# Sheet1.net
KiCad netlist of a schematic drawn in Altium Designer
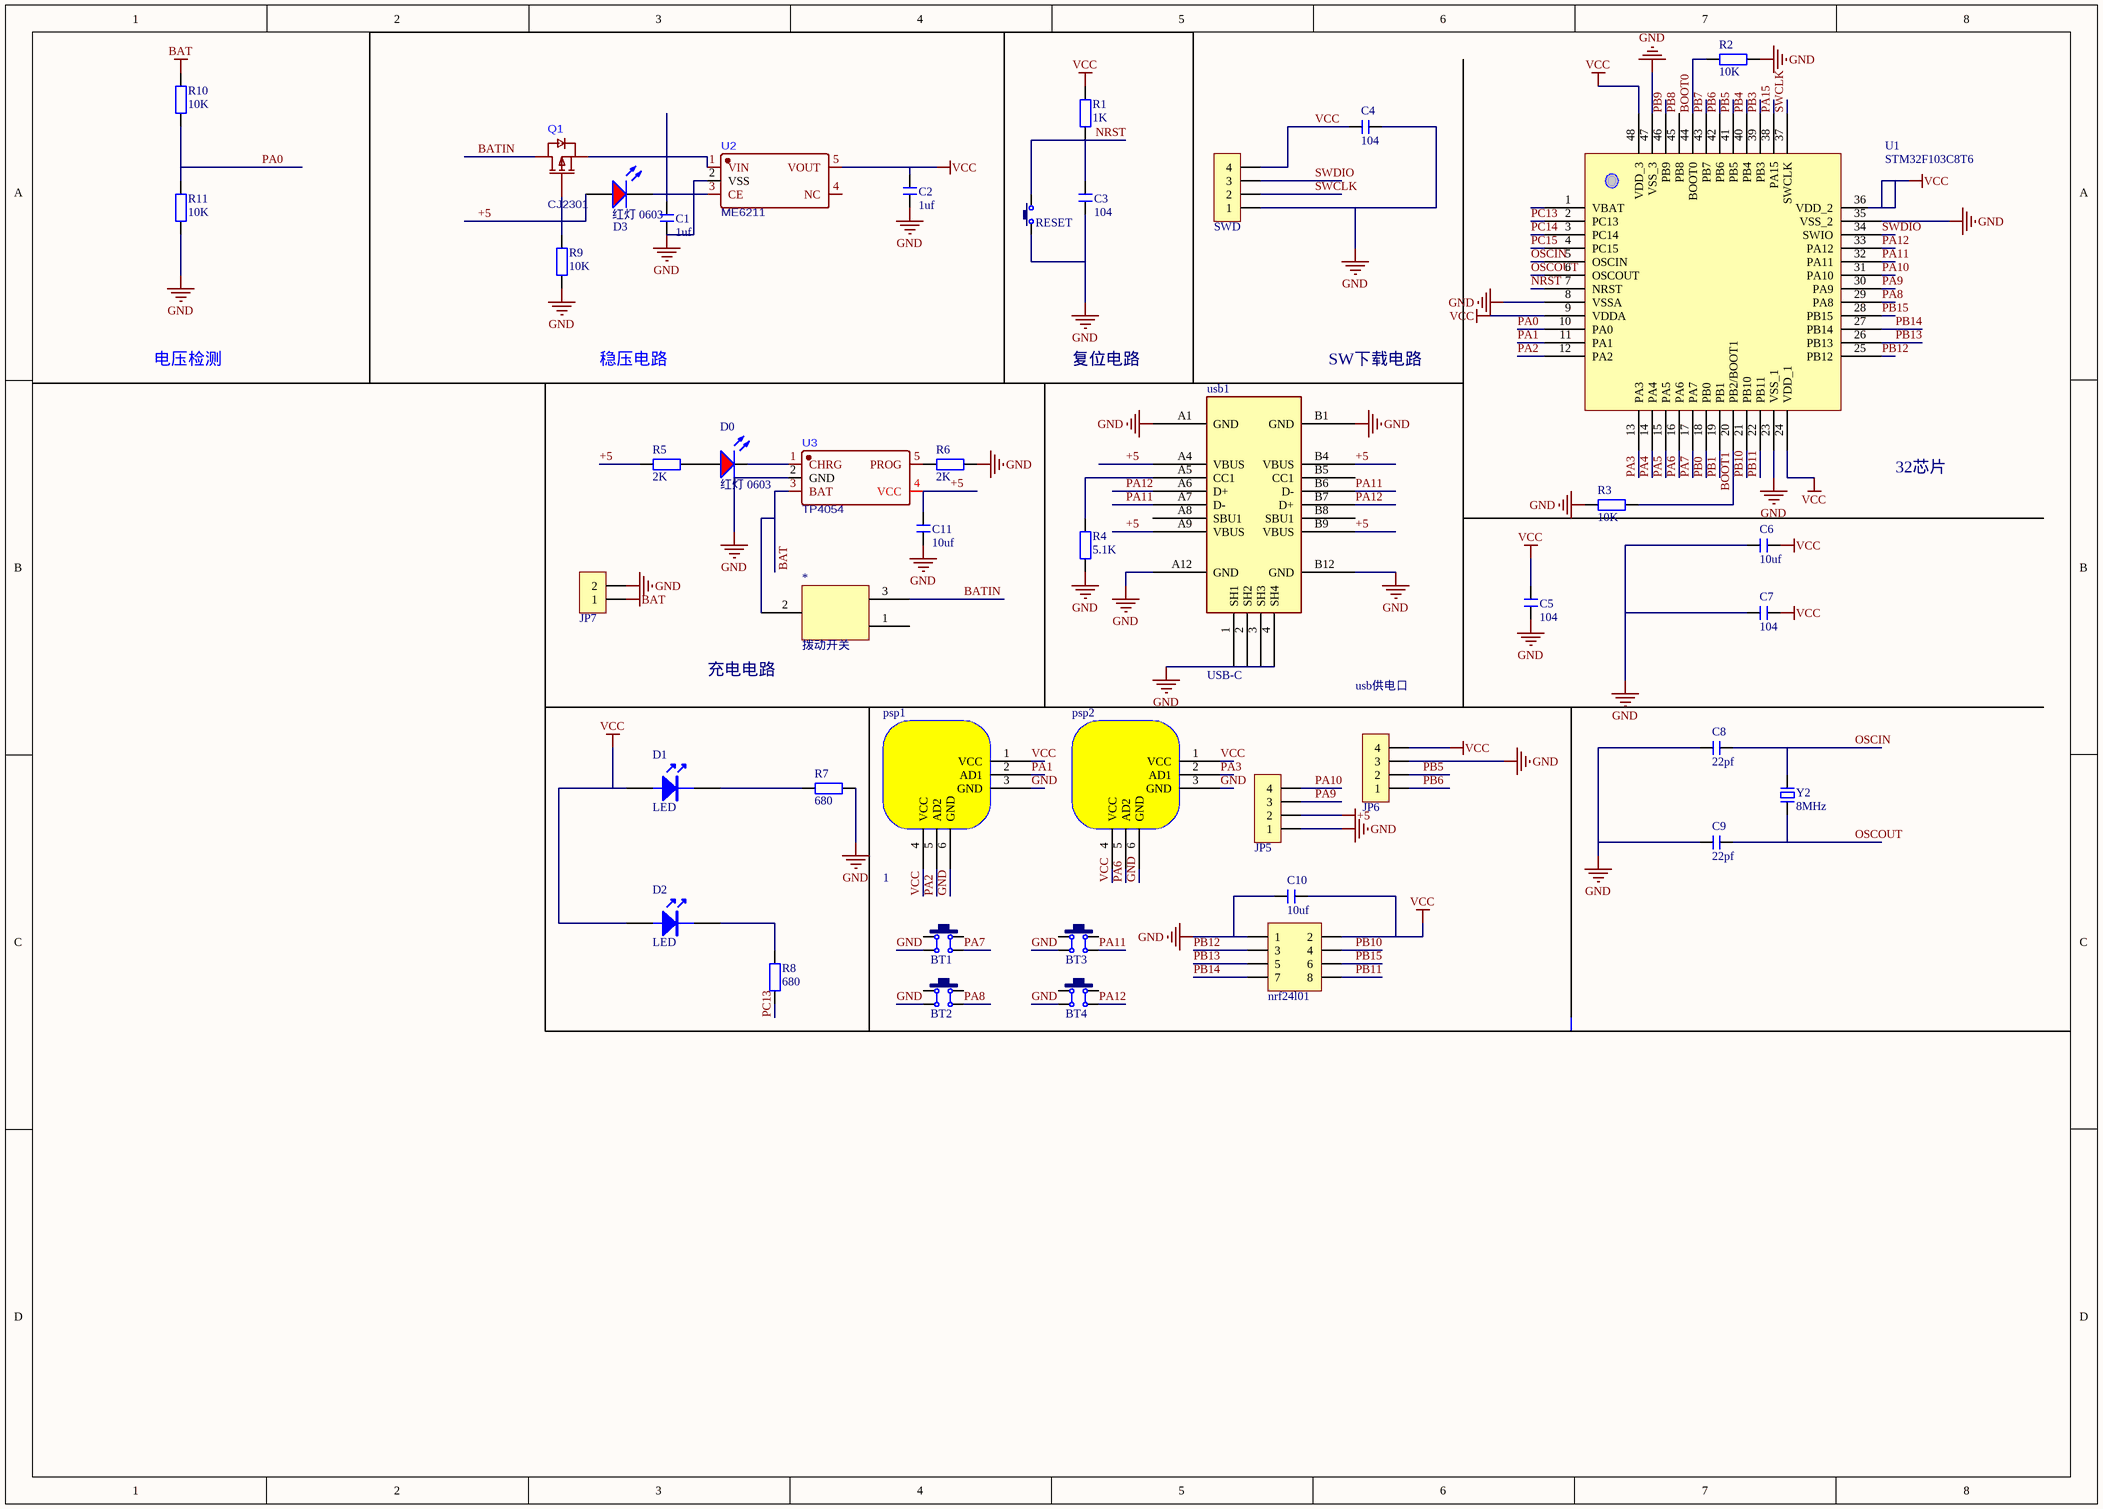
[diagram p0: Sheet1.SchDoc]

(export (version "E")
  (design (tool "Eeschema 10.0.6"))
  (components
    (comp (ref "*") (value "拨动开关") (footprint "SS-12F23") (libsource (lib "拨动开关") (part "拨动开关")))
    (comp (ref "BT1")
      (value "6x6x5")
      (footprint "TSW DIP-6*6*6")
      (description "直插6x6轻触开关")
      (fields (field (name "版权归属") "封装库来自淘宝 ID：黄晶宝石"))
      (libsource (lib "0.7 - 常用按键-开关") (part "TSW DIP-6x6"))
    )
    (comp (ref "BT2")
      (value "6x6x5")
      (footprint "TSW DIP-6*6*6")
      (description "直插6x6轻触开关")
      (fields (field (name "版权归属") "封装库来自淘宝 ID：黄晶宝石"))
      (libsource (lib "0.7 - 常用按键-开关") (part "TSW DIP-6x6"))
    )
    (comp (ref "BT3")
      (value "6x6x5")
      (footprint "TSW DIP-6*6*6")
      (description "直插6x6轻触开关")
      (fields (field (name "版权归属") "封装库来自淘宝 ID：黄晶宝石"))
      (libsource (lib "0.7 - 常用按键-开关") (part "TSW DIP-6x6"))
    )
    (comp (ref "BT4")
      (value "6x6x5")
      (footprint "TSW DIP-6*6*6")
      (description "直插6x6轻触开关")
      (fields (field (name "版权归属") "封装库来自淘宝 ID：黄晶宝石"))
      (libsource (lib "0.7 - 常用按键-开关") (part "TSW DIP-6x6"))
    )
    (comp (ref "C1")
      (value "1uf")
      (footprint "C 0603_L")
      (description "贴片电容")
      (libsource (lib "0.1 - 电阻-电容-电感") (part "C"))
    )
    (comp (ref "C2")
      (value "1uf")
      (footprint "C 0603_L")
      (description "贴片电容")
      (libsource (lib "0.1 - 电阻-电容-电感") (part "C"))
    )
    (comp (ref "C3")
      (value "104")
      (footprint "C 0603_L")
      (description "贴片电容")
      (libsource (lib "0.1 - 电阻-电容-电感") (part "C"))
    )
    (comp (ref "C4")
      (value "104")
      (footprint "C 0603_L")
      (description "贴片电容")
      (libsource (lib "0.1 - 电阻-电容-电感") (part "C"))
    )
    (comp (ref "C5")
      (value "104")
      (footprint "C 0603_L")
      (description "贴片电容")
      (libsource (lib "0.1 - 电阻-电容-电感") (part "C"))
    )
    (comp (ref "C6")
      (value "10uf")
      (footprint "C 0603_L")
      (description "贴片电容")
      (libsource (lib "0.1 - 电阻-电容-电感") (part "C"))
    )
    (comp (ref "C7")
      (value "104")
      (footprint "C 0603_L")
      (description "贴片电容")
      (libsource (lib "0.1 - 电阻-电容-电感") (part "C"))
    )
    (comp (ref "C8")
      (value "22pf")
      (footprint "C 0603_L")
      (description "贴片电容")
      (libsource (lib "0.1 - 电阻-电容-电感") (part "C"))
    )
    (comp (ref "C9")
      (value "22pf")
      (footprint "C 0603_L")
      (description "贴片电容")
      (libsource (lib "0.1 - 电阻-电容-电感") (part "C"))
    )
    (comp (ref "C10")
      (value "10uf")
      (footprint "C 0603_L")
      (description "贴片电容")
      (libsource (lib "0.1 - 电阻-电容-电感") (part "C"))
    )
    (comp (ref "C11")
      (value "10uf")
      (footprint "C 0603_L")
      (description "贴片电容")
      (libsource (lib "0.1 - 电阻-电容-电感") (part "C"))
    )
    (comp (ref "D0")
      (value "红灯 0603")
      (footprint "LC-0603_LED_S1")
      (description "发光二极管")
      (libsource (lib "STM32F103ZET6库文件") (part "0603 红灯"))
    )
    (comp (ref "D1") (value "LED") (footprint "LED 0805G") (libsource (lib "stm32原理图库") (part "LED")))
    (comp (ref "D2") (value "LED") (footprint "LED 0805G") (libsource (lib "stm32原理图库") (part "LED")))
    (comp (ref "D3")
      (value "红灯 0603")
      (footprint "LC-0603_LED_S1")
      (description "发光二极管")
      (libsource (lib "STM32F103ZET6库文件") (part "0603 红灯"))
    )
    (comp (ref "JP5")
      (value "HDR-1X4")
      (footprint "HDR2.54-M-LI-4P")
      (description "4P接插件")
      (fields (field (name "版权归属") "封装库来自淘宝 ID：黄晶宝石"))
      (libsource (lib "5.3 - 接插件-脚距2.54 (100mil) ") (part "Header 4"))
    )
    (comp (ref "JP6")
      (value "HDR-1X4")
      (footprint "HDR2.54-M-LI-4P")
      (description "4P接插件")
      (fields (field (name "版权归属") "封装库来自淘宝 ID：黄晶宝石"))
      (libsource (lib "5.3 - 接插件-脚距2.54 (100mil) ") (part "Header 4"))
    )
    (comp (ref "JP7")
      (value "HDR-1X2")
      (footprint "XH2.54-WI-2P")
      (description "2P接插件")
      (fields (field (name "版权归属") "封装库来自淘宝 ID：黄晶宝石"))
      (libsource (lib "5.3 - 接插件-脚距2.54 (100mil) ") (part "Header 2"))
    )
    (comp (ref "nrf24l01")
      (value "Header 4X2")
      (footprint "HDR2.54-LI-2x4P")
      (description "4*2P接插件")
      (fields (field (name "版权归属") "封装库来自淘宝 ID：黄晶宝石"))
      (libsource (lib "5.3 - 接插件-脚距2.54 (100mil) ") (part "Header 4X2"))
    )
    (comp (ref "psp1") (value "1") (footprint "PSP摇杆") (libsource (lib "PSP摇杆") (part "PSP摇杆")))
    (comp (ref "psp2") (value "~") (footprint "PSP摇杆") (libsource (lib "PSP摇杆") (part "PSP摇杆")))
    (comp (ref "Q1") (value "CJ2301") (footprint "CJ2301") (libsource (lib "CJ2301") (part "CJ2301")))
    (comp (ref "R1")
      (value "1K")
      (footprint "R 0603_L")
      (description "贴片电阻")
      (fields (field (name "版权归属") "来自淘宝 ID：黄晶宝石"))
      (libsource (lib "0.1 - 电阻-电容-电感") (part "R"))
    )
    (comp (ref "R2")
      (value "10K")
      (footprint "R 0603_L")
      (description "贴片电阻")
      (fields (field (name "版权归属") "来自淘宝 ID：黄晶宝石"))
      (libsource (lib "0.1 - 电阻-电容-电感") (part "R"))
    )
    (comp (ref "R3")
      (value "10K")
      (footprint "R 0603_L")
      (description "贴片电阻")
      (fields (field (name "版权归属") "来自淘宝 ID：黄晶宝石"))
      (libsource (lib "0.1 - 电阻-电容-电感") (part "R"))
    )
    (comp (ref "R4")
      (value "5.1K")
      (footprint "R 0603_L")
      (description "贴片电阻")
      (fields (field (name "版权归属") "来自淘宝 ID：黄晶宝石"))
      (libsource (lib "0.1 - 电阻-电容-电感") (part "R"))
    )
    (comp (ref "R5")
      (value "2K")
      (footprint "R 0603_L")
      (description "贴片电阻")
      (fields (field (name "版权归属") "来自淘宝 ID：黄晶宝石"))
      (libsource (lib "0.1 - 电阻-电容-电感") (part "R"))
    )
    (comp (ref "R6")
      (value "2K")
      (footprint "R 0603_L")
      (description "贴片电阻")
      (fields (field (name "版权归属") "来自淘宝 ID：黄晶宝石"))
      (libsource (lib "0.1 - 电阻-电容-电感") (part "R"))
    )
    (comp (ref "R7")
      (value "680")
      (footprint "R 0603_L")
      (description "贴片电阻")
      (fields (field (name "版权归属") "来自淘宝 ID：黄晶宝石"))
      (libsource (lib "0.1 - 电阻-电容-电感") (part "R"))
    )
    (comp (ref "R8")
      (value "680")
      (footprint "R 0603_L")
      (description "贴片电阻")
      (fields (field (name "版权归属") "来自淘宝 ID：黄晶宝石"))
      (libsource (lib "0.1 - 电阻-电容-电感") (part "R"))
    )
    (comp (ref "R9")
      (value "10K")
      (footprint "R 0603_L")
      (description "贴片电阻")
      (fields (field (name "版权归属") "来自淘宝 ID：黄晶宝石"))
      (libsource (lib "0.1 - 电阻-电容-电感") (part "R"))
    )
    (comp (ref "R10")
      (value "10K")
      (footprint "R 0603_L")
      (description "贴片电阻")
      (fields (field (name "版权归属") "来自淘宝 ID：黄晶宝石"))
      (libsource (lib "0.1 - 电阻-电容-电感") (part "R"))
    )
    (comp (ref "R11")
      (value "10K")
      (footprint "R 0603_L")
      (description "贴片电阻")
      (fields (field (name "版权归属") "来自淘宝 ID：黄晶宝石"))
      (libsource (lib "0.1 - 电阻-电容-电感") (part "R"))
    )
    (comp (ref "RESET")
      (value "3x6x5")
      (footprint "TSW SMD-3*6*2.5")
      (description "3x6轻触开关")
      (fields (field (name "版权归属") "封装库来自淘宝 ID：黄晶宝石"))
      (libsource (lib "0.7 - 常用按键-开关") (part "TSW 3x6"))
    )
    (comp (ref "SWD")
      (value "HDR-1X4")
      (footprint "HDR2.54-WI-4P")
      (description "4P接插件")
      (fields (field (name "版权归属") "封装库来自淘宝 ID：黄晶宝石"))
      (libsource (lib "5.3 - 接插件-脚距2.54 (100mil) ") (part "Header 4"))
    )
    (comp (ref "U1")
      (value "STM32F103C8T6")
      (footprint "TQFP48 7x7_L")
      (libsource (lib "stm32原理图库") (part "STM32F103C8T6"))
    )
    (comp (ref "U2")
      (value "ME6211")
      (footprint "SOT23-5")
      (libsource (lib "ME6211C25M5G-N") (part "ME6211C25M5G-N"))
    )
    (comp (ref "U3") (value "TP4054") (footprint "SOT23-5") (libsource (lib "TP4054") (part "TP4054")))
    (comp (ref "usb1") (value "USB-C") (footprint "USB-C") (libsource (lib "USB-C") (part "USB-C")))
    (comp (ref "Y2")
      (value "8MHz")
      (footprint "OSC HC-49S")
      (description "2脚无源脚晶振")
      (fields (field (name "版权归属") "封装库来自淘宝卖家 ID：黄晶宝石"))
      (libsource (lib "2.0 - 保险丝-晶振-光耦") (part "XTAL-2P"))
    )
  )
  (nets
    (net (code "1") (name "+5") (class "Default")
      (node (ref "C11") (pin "2") (pinfunction "2_2") (pintype "passive"))
      (node (ref "D3") (pin "A") (pinfunction "A_A") (pintype "passive"))
      (node (ref "JP5") (pin "2") (pinfunction "2_2") (pintype "passive"))
      (node (ref "Q1") (pin "1") (pinfunction "G_1") (pintype "passive"))
      (node (ref "R5") (pin "1") (pinfunction "1_1") (pintype "passive"))
      (node (ref "R9") (pin "2") (pinfunction "2_2") (pintype "passive"))
      (node (ref "U3") (pin "4") (pinfunction "VCC_4") (pintype "passive"))
      (node (ref "usb1") (pin "A4") (pinfunction "VBUS_A4") (pintype "open_emitter"))
      (node (ref "usb1") (pin "A9") (pinfunction "VBUS_A9") (pintype "open_emitter"))
      (node (ref "usb1") (pin "B4") (pinfunction "VBUS_B4") (pintype "open_emitter"))
      (node (ref "usb1") (pin "B9") (pinfunction "VBUS_B9") (pintype "open_emitter"))
    )
    (net (code "2") (name "/BATIN") (class "Default")
      (node (ref "*") (pin "3") (pintype "passive"))
      (node (ref "Q1") (pin "3") (pinfunction "D_3") (pintype "passive"))
    )
    (net (code "3") (name "/BOOT0") (class "Default")
      (node (ref "R2") (pin "1") (pinfunction "1_1") (pintype "passive"))
      (node (ref "U1") (pin "44") (pinfunction "BOOT0_44") (pintype "passive"))
    )
    (net (code "4") (name "/BOOT1") (class "Default")
      (node (ref "R3") (pin "2") (pinfunction "2_2") (pintype "passive"))
      (node (ref "U1") (pin "20") (pinfunction "PB2/BOOT1_20") (pintype "passive"))
    )
    (net (code "5") (name "/NRST") (class "Default")
      (node (ref "C3") (pin "2") (pinfunction "2_2") (pintype "passive"))
      (node (ref "R1") (pin "1") (pinfunction "1_1") (pintype "passive"))
      (node (ref "RESET") (pin "2") (pinfunction "2_2") (pintype "passive"))
      (node (ref "U1") (pin "7") (pinfunction "NRST_7") (pintype "passive"))
    )
    (net (code "6") (name "/OSCIN") (class "Default")
      (node (ref "C8") (pin "2") (pinfunction "2_2") (pintype "passive"))
      (node (ref "U1") (pin "5") (pinfunction "OSCIN_5") (pintype "passive"))
      (node (ref "Y2") (pin "2") (pinfunction "2_2") (pintype "passive"))
    )
    (net (code "7") (name "/OSCOUT") (class "Default")
      (node (ref "C9") (pin "2") (pinfunction "2_2") (pintype "passive"))
      (node (ref "U1") (pin "6") (pinfunction "OSCOUT_6") (pintype "passive"))
      (node (ref "Y2") (pin "1") (pinfunction "1_1") (pintype "passive"))
    )
    (net (code "8") (name "/PA0") (class "Default")
      (node (ref "R10") (pin "1") (pinfunction "1_1") (pintype "passive"))
      (node (ref "R11") (pin "2") (pinfunction "2_2") (pintype "passive"))
      (node (ref "U1") (pin "10") (pinfunction "PA0_10") (pintype "passive"))
    )
    (net (code "9") (name "/PA1") (class "Default")
      (node (ref "U1") (pin "11") (pinfunction "PA1_11") (pintype "passive"))
      (node (ref "psp1") (pin "2") (pinfunction "AD1_2") (pintype "passive"))
    )
    (net (code "10") (name "/PA2") (class "Default")
      (node (ref "U1") (pin "12") (pinfunction "PA2_12") (pintype "passive"))
      (node (ref "psp1") (pin "5") (pinfunction "AD2_5") (pintype "passive"))
    )
    (net (code "11") (name "/PA3") (class "Default")
      (node (ref "U1") (pin "13") (pinfunction "PA3_13") (pintype "passive"))
      (node (ref "psp2") (pin "2") (pinfunction "AD1_2") (pintype "passive"))
    )
    (net (code "12") (name "/PA4") (class "Default")
      (node (ref "U1") (pin "14") (pinfunction "PA4_14") (pintype "passive"))
    )
    (net (code "13") (name "/PA5") (class "Default")
      (node (ref "U1") (pin "15") (pinfunction "PA5_15") (pintype "passive"))
    )
    (net (code "14") (name "/PA6") (class "Default")
      (node (ref "U1") (pin "16") (pinfunction "PA6_16") (pintype "passive"))
      (node (ref "psp2") (pin "5") (pinfunction "AD2_5") (pintype "passive"))
    )
    (net (code "15") (name "/PA7") (class "Default")
      (node (ref "BT1") (pin "3") (pinfunction "3_3") (pintype "passive"))
      (node (ref "U1") (pin "17") (pinfunction "PA7_17") (pintype "passive"))
    )
    (net (code "16") (name "/PA8") (class "Default")
      (node (ref "BT2") (pin "3") (pinfunction "3_3") (pintype "passive"))
      (node (ref "U1") (pin "29") (pinfunction "PA8_29") (pintype "passive"))
    )
    (net (code "17") (name "/PA9") (class "Default")
      (node (ref "JP5") (pin "3") (pinfunction "3_3") (pintype "passive"))
      (node (ref "U1") (pin "30") (pinfunction "PA9_30") (pintype "passive"))
    )
    (net (code "18") (name "/PA10") (class "Default")
      (node (ref "JP5") (pin "4") (pinfunction "4_4") (pintype "passive"))
      (node (ref "U1") (pin "31") (pinfunction "PA10_31") (pintype "passive"))
    )
    (net (code "19") (name "/PA11") (class "Default")
      (node (ref "BT3") (pin "3") (pinfunction "3_3") (pintype "passive"))
      (node (ref "U1") (pin "32") (pinfunction "PA11_32") (pintype "passive"))
      (node (ref "usb1") (pin "A7") (pinfunction "D-_A7") (pintype "open_emitter"))
      (node (ref "usb1") (pin "B6") (pinfunction "D-_B6") (pintype "open_emitter"))
    )
    (net (code "20") (name "/PA12") (class "Default")
      (node (ref "BT4") (pin "3") (pinfunction "3_3") (pintype "passive"))
      (node (ref "U1") (pin "33") (pinfunction "PA12_33") (pintype "passive"))
      (node (ref "usb1") (pin "A6") (pinfunction "D+_A6") (pintype "open_emitter"))
      (node (ref "usb1") (pin "B7") (pinfunction "D+_B7") (pintype "open_emitter"))
    )
    (net (code "21") (name "/PA15") (class "Default")
      (node (ref "U1") (pin "38") (pinfunction "PA15_38") (pintype "passive"))
    )
    (net (code "22") (name "/PB0") (class "Default")
      (node (ref "U1") (pin "18") (pinfunction "PB0_18") (pintype "passive"))
    )
    (net (code "23") (name "/PB1") (class "Default")
      (node (ref "U1") (pin "19") (pinfunction "PB1_19") (pintype "passive"))
    )
    (net (code "24") (name "/PB3") (class "Default")
      (node (ref "U1") (pin "39") (pinfunction "PB3_39") (pintype "passive"))
    )
    (net (code "25") (name "/PB4") (class "Default")
      (node (ref "U1") (pin "40") (pinfunction "PB4_40") (pintype "passive"))
    )
    (net (code "26") (name "/PB5") (class "Default")
      (node (ref "JP6") (pin "2") (pinfunction "2_2") (pintype "passive"))
      (node (ref "U1") (pin "41") (pinfunction "PB5_41") (pintype "passive"))
    )
    (net (code "27") (name "/PB6") (class "Default")
      (node (ref "JP6") (pin "1") (pinfunction "1_1") (pintype "passive"))
      (node (ref "U1") (pin "42") (pinfunction "PB6_42") (pintype "passive"))
    )
    (net (code "28") (name "/PB7") (class "Default")
      (node (ref "U1") (pin "43") (pinfunction "PB7_43") (pintype "passive"))
    )
    (net (code "29") (name "/PB8") (class "Default")
      (node (ref "U1") (pin "45") (pinfunction "PB8_45") (pintype "passive"))
    )
    (net (code "30") (name "/PB9") (class "Default")
      (node (ref "U1") (pin "46") (pinfunction "PB9_46") (pintype "passive"))
    )
    (net (code "31") (name "/PB10") (class "Default")
      (node (ref "U1") (pin "21") (pinfunction "PB10_21") (pintype "passive"))
      (node (ref "nrf24l01") (pin "4") (pinfunction "4_4") (pintype "passive"))
    )
    (net (code "32") (name "/PB11") (class "Default")
      (node (ref "U1") (pin "22") (pinfunction "PB11_22") (pintype "passive"))
      (node (ref "nrf24l01") (pin "8") (pinfunction "8_8") (pintype "passive"))
    )
    (net (code "33") (name "/PB12") (class "Default")
      (node (ref "U1") (pin "25") (pinfunction "PB12_25") (pintype "passive"))
      (node (ref "nrf24l01") (pin "3") (pinfunction "3_3") (pintype "passive"))
    )
    (net (code "34") (name "/PB13") (class "Default")
      (node (ref "U1") (pin "26") (pinfunction "PB13_26") (pintype "passive"))
      (node (ref "nrf24l01") (pin "5") (pinfunction "5_5") (pintype "passive"))
    )
    (net (code "35") (name "/PB14") (class "Default")
      (node (ref "U1") (pin "27") (pinfunction "PB14_27") (pintype "passive"))
      (node (ref "nrf24l01") (pin "7") (pinfunction "7_7") (pintype "passive"))
    )
    (net (code "36") (name "/PB15") (class "Default")
      (node (ref "U1") (pin "28") (pinfunction "PB15_28") (pintype "passive"))
      (node (ref "nrf24l01") (pin "6") (pinfunction "6_6") (pintype "passive"))
    )
    (net (code "37") (name "/PC13") (class "Default")
      (node (ref "R8") (pin "2") (pinfunction "2_2") (pintype "passive"))
      (node (ref "U1") (pin "2") (pinfunction "PC13_2") (pintype "passive"))
    )
    (net (code "38") (name "/PC14") (class "Default")
      (node (ref "U1") (pin "3") (pinfunction "PC14_3") (pintype "passive"))
    )
    (net (code "39") (name "/PC15") (class "Default")
      (node (ref "U1") (pin "4") (pinfunction "PC15_4") (pintype "passive"))
    )
    (net (code "40") (name "/SWCLK") (class "Default")
      (node (ref "SWD") (pin "2") (pinfunction "2_2") (pintype "passive"))
      (node (ref "U1") (pin "37") (pinfunction "SWCLK_37") (pintype "passive"))
    )
    (net (code "41") (name "/SWDIO") (class "Default")
      (node (ref "SWD") (pin "3") (pinfunction "3_3") (pintype "passive"))
      (node (ref "U1") (pin "34") (pinfunction "SWIO_34") (pintype "passive"))
    )
    (net (code "42") (name "BAT") (class "Default")
      (node (ref "*") (pin "2") (pintype "passive"))
      (node (ref "JP7") (pin "1") (pinfunction "1_1") (pintype "passive"))
      (node (ref "R10") (pin "2") (pinfunction "2_2") (pintype "passive"))
      (node (ref "U3") (pin "3") (pinfunction "BAT_3") (pintype "passive"))
    )
    (net (code "43") (name "GND") (class "Default")
      (node (ref "BT1") (pin "4") (pinfunction "4_4") (pintype "passive"))
      (node (ref "BT2") (pin "4") (pinfunction "4_4") (pintype "passive"))
      (node (ref "BT3") (pin "4") (pinfunction "4_4") (pintype "passive"))
      (node (ref "BT4") (pin "4") (pinfunction "4_4") (pintype "passive"))
      (node (ref "C1") (pin "1") (pinfunction "1_1") (pintype "passive"))
      (node (ref "C10") (pin "1") (pinfunction "1_1") (pintype "passive"))
      (node (ref "C11") (pin "1") (pinfunction "1_1") (pintype "passive"))
      (node (ref "C2") (pin "1") (pinfunction "1_1") (pintype "passive"))
      (node (ref "C3") (pin "1") (pinfunction "1_1") (pintype "passive"))
      (node (ref "C4") (pin "1") (pinfunction "1_1") (pintype "passive"))
      (node (ref "C5") (pin "1") (pinfunction "1_1") (pintype "passive"))
      (node (ref "C6") (pin "2") (pinfunction "2_2") (pintype "passive"))
      (node (ref "C7") (pin "2") (pinfunction "2_2") (pintype "passive"))
      (node (ref "C8") (pin "1") (pinfunction "1_1") (pintype "passive"))
      (node (ref "C9") (pin "1") (pinfunction "1_1") (pintype "passive"))
      (node (ref "JP5") (pin "1") (pinfunction "1_1") (pintype "passive"))
      (node (ref "JP6") (pin "3") (pinfunction "3_3") (pintype "passive"))
      (node (ref "JP7") (pin "2") (pinfunction "2_2") (pintype "passive"))
      (node (ref "R11") (pin "1") (pinfunction "1_1") (pintype "passive"))
      (node (ref "R2") (pin "2") (pinfunction "2_2") (pintype "passive"))
      (node (ref "R3") (pin "1") (pinfunction "1_1") (pintype "passive"))
      (node (ref "R4") (pin "1") (pinfunction "1_1") (pintype "passive"))
      (node (ref "R6") (pin "2") (pinfunction "2_2") (pintype "passive"))
      (node (ref "R7") (pin "1") (pinfunction "1_1") (pintype "passive"))
      (node (ref "R9") (pin "1") (pinfunction "1_1") (pintype "passive"))
      (node (ref "RESET") (pin "1") (pinfunction "1_1") (pintype "passive"))
      (node (ref "SWD") (pin "1") (pinfunction "1_1") (pintype "passive"))
      (node (ref "U1") (pin "23") (pinfunction "VSS_1_23") (pintype "passive"))
      (node (ref "U1") (pin "35") (pinfunction "VSS_2_35") (pintype "passive"))
      (node (ref "U1") (pin "47") (pinfunction "VSS_3_47") (pintype "passive"))
      (node (ref "U1") (pin "8") (pinfunction "VSSA_8") (pintype "passive"))
      (node (ref "U2") (pin "2") (pinfunction "VSS_2") (pintype "passive"))
      (node (ref "U3") (pin "2") (pinfunction "GND_2") (pintype "passive"))
      (node (ref "nrf24l01") (pin "1") (pinfunction "1_1") (pintype "passive"))
      (node (ref "psp1") (pin "3") (pinfunction "GND_3") (pintype "passive"))
      (node (ref "psp1") (pin "6") (pinfunction "GND_6") (pintype "passive"))
      (node (ref "psp2") (pin "3") (pinfunction "GND_3") (pintype "passive"))
      (node (ref "psp2") (pin "6") (pinfunction "GND_6") (pintype "passive"))
      (node (ref "usb1") (pin "1") (pinfunction "SH1_1") (pintype "open_emitter"))
      (node (ref "usb1") (pin "2") (pinfunction "SH2_2") (pintype "open_emitter"))
      (node (ref "usb1") (pin "3") (pinfunction "SH3_3") (pintype "open_emitter"))
      (node (ref "usb1") (pin "4") (pinfunction "SH4_4") (pintype "open_emitter"))
      (node (ref "usb1") (pin "A1") (pinfunction "GND_A1") (pintype "open_emitter"))
      (node (ref "usb1") (pin "A12") (pinfunction "GND_A12") (pintype "open_emitter"))
      (node (ref "usb1") (pin "B1") (pinfunction "GND_B1") (pintype "open_emitter"))
      (node (ref "usb1") (pin "B12") (pinfunction "GND_B12") (pintype "open_emitter"))
    )
    (net (code "44") (name "Net-(D0-PadA)") (class "Default")
      (node (ref "D0") (pin "A") (pinfunction "A_A") (pintype "passive"))
      (node (ref "R5") (pin "2") (pinfunction "2_2") (pintype "passive"))
    )
    (net (code "45") (name "Net-(D1-Pad2)") (class "Default")
      (node (ref "D1") (pin "2") (pinfunction "2_2") (pintype "passive"))
      (node (ref "R7") (pin "2") (pinfunction "2_2") (pintype "passive"))
    )
    (net (code "46") (name "Net-(D2-Pad2)") (class "Default")
      (node (ref "D2") (pin "2") (pinfunction "2_2") (pintype "passive"))
      (node (ref "R8") (pin "1") (pinfunction "1_1") (pintype "passive"))
    )
    (net (code "47") (name "Net-(Q1-S)") (class "Default")
      (node (ref "C1") (pin "2") (pinfunction "2_2") (pintype "passive"))
      (node (ref "D3") (pin "K") (pinfunction "K_K") (pintype "passive"))
      (node (ref "Q1") (pin "2") (pinfunction "S_2") (pintype "passive"))
      (node (ref "U2") (pin "1") (pinfunction "VIN_1") (pintype "passive"))
      (node (ref "U2") (pin "3") (pinfunction "CE_3") (pintype "passive"))
    )
    (net (code "48") (name "Net-(R4-Pad2)") (class "Default")
      (node (ref "R4") (pin "2") (pinfunction "2_2") (pintype "passive"))
      (node (ref "usb1") (pin "A5") (pinfunction "CC1_A5") (pintype "open_emitter"))
    )
    (net (code "49") (name "Net-(U3-CHRG)") (class "Default")
      (node (ref "D0") (pin "K") (pinfunction "K_K") (pintype "passive"))
      (node (ref "U3") (pin "1") (pinfunction "CHRG_1") (pintype "passive"))
    )
    (net (code "50") (name "Net-(U3-PROG)") (class "Default")
      (node (ref "R6") (pin "1") (pinfunction "1_1") (pintype "passive"))
      (node (ref "U3") (pin "5") (pinfunction "PROG_5") (pintype "passive"))
    )
    (net (code "51") (name "VCC") (class "Default")
      (node (ref "C10") (pin "2") (pinfunction "2_2") (pintype "passive"))
      (node (ref "C2") (pin "2") (pinfunction "2_2") (pintype "passive"))
      (node (ref "C4") (pin "2") (pinfunction "2_2") (pintype "passive"))
      (node (ref "C5") (pin "2") (pinfunction "2_2") (pintype "passive"))
      (node (ref "C6") (pin "1") (pinfunction "1_1") (pintype "passive"))
      (node (ref "C7") (pin "1") (pinfunction "1_1") (pintype "passive"))
      (node (ref "D1") (pin "1") (pinfunction "1_1") (pintype "passive"))
      (node (ref "D2") (pin "1") (pinfunction "1_1") (pintype "passive"))
      (node (ref "JP6") (pin "4") (pinfunction "4_4") (pintype "passive"))
      (node (ref "R1") (pin "2") (pinfunction "2_2") (pintype "passive"))
      (node (ref "SWD") (pin "4") (pinfunction "4_4") (pintype "passive"))
      (node (ref "U1") (pin "24") (pinfunction "VDD_1_24") (pintype "passive"))
      (node (ref "U1") (pin "36") (pinfunction "VDD_2_36") (pintype "passive"))
      (node (ref "U1") (pin "48") (pinfunction "VDD_3_48") (pintype "passive"))
      (node (ref "U1") (pin "9") (pinfunction "VDDA_9") (pintype "passive"))
      (node (ref "U2") (pin "5") (pinfunction "VOUT_5") (pintype "passive"))
      (node (ref "nrf24l01") (pin "2") (pinfunction "2_2") (pintype "passive"))
      (node (ref "psp1") (pin "1") (pinfunction "VCC_1") (pintype "passive"))
      (node (ref "psp1") (pin "4") (pinfunction "VCC_4") (pintype "passive"))
      (node (ref "psp2") (pin "1") (pinfunction "VCC_1") (pintype "passive"))
      (node (ref "psp2") (pin "4") (pinfunction "VCC_4") (pintype "passive"))
    )
    (net (code "52") (name "unconnected-(*-Pad1)") (class "Default")
      (node (ref "*") (pin "1") (pintype "passive"))
    )
    (net (code "53") (name "unconnected-(BT1-Pad1)") (class "Default")
      (node (ref "BT1") (pin "1") (pinfunction "1_1") (pintype "passive"))
    )
    (net (code "54") (name "unconnected-(BT1-Pad2)") (class "Default")
      (node (ref "BT1") (pin "2") (pinfunction "2_2") (pintype "passive"))
    )
    (net (code "55") (name "unconnected-(BT2-Pad1)") (class "Default")
      (node (ref "BT2") (pin "1") (pinfunction "1_1") (pintype "passive"))
    )
    (net (code "56") (name "unconnected-(BT2-Pad2)") (class "Default")
      (node (ref "BT2") (pin "2") (pinfunction "2_2") (pintype "passive"))
    )
    (net (code "57") (name "unconnected-(BT3-Pad1)") (class "Default")
      (node (ref "BT3") (pin "1") (pinfunction "1_1") (pintype "passive"))
    )
    (net (code "58") (name "unconnected-(BT3-Pad2)") (class "Default")
      (node (ref "BT3") (pin "2") (pinfunction "2_2") (pintype "passive"))
    )
    (net (code "59") (name "unconnected-(BT4-Pad1)") (class "Default")
      (node (ref "BT4") (pin "1") (pinfunction "1_1") (pintype "passive"))
    )
    (net (code "60") (name "unconnected-(BT4-Pad2)") (class "Default")
      (node (ref "BT4") (pin "2") (pinfunction "2_2") (pintype "passive"))
    )
    (net (code "61") (name "unconnected-(U1-VBAT-Pad1)") (class "Default")
      (node (ref "U1") (pin "1") (pinfunction "VBAT_1") (pintype "passive"))
    )
    (net (code "62") (name "unconnected-(U2-NC-Pad4)") (class "Default")
      (node (ref "U2") (pin "4") (pinfunction "NC_4") (pintype "passive"))
    )
    (net (code "63") (name "unconnected-(usb1-CC1-PadB5)") (class "Default")
      (node (ref "usb1") (pin "B5") (pinfunction "CC1_B5") (pintype "open_emitter"))
    )
    (net (code "64") (name "unconnected-(usb1-SBU1-PadA8)") (class "Default")
      (node (ref "usb1") (pin "A8") (pinfunction "SBU1_A8") (pintype "open_emitter"))
    )
    (net (code "65") (name "unconnected-(usb1-SBU1-PadB8)") (class "Default")
      (node (ref "usb1") (pin "B8") (pinfunction "SBU1_B8") (pintype "open_emitter"))
    )
  )
)
